# 7_DDR3L.net
KiCad netlist of a schematic drawn in Altium Designer
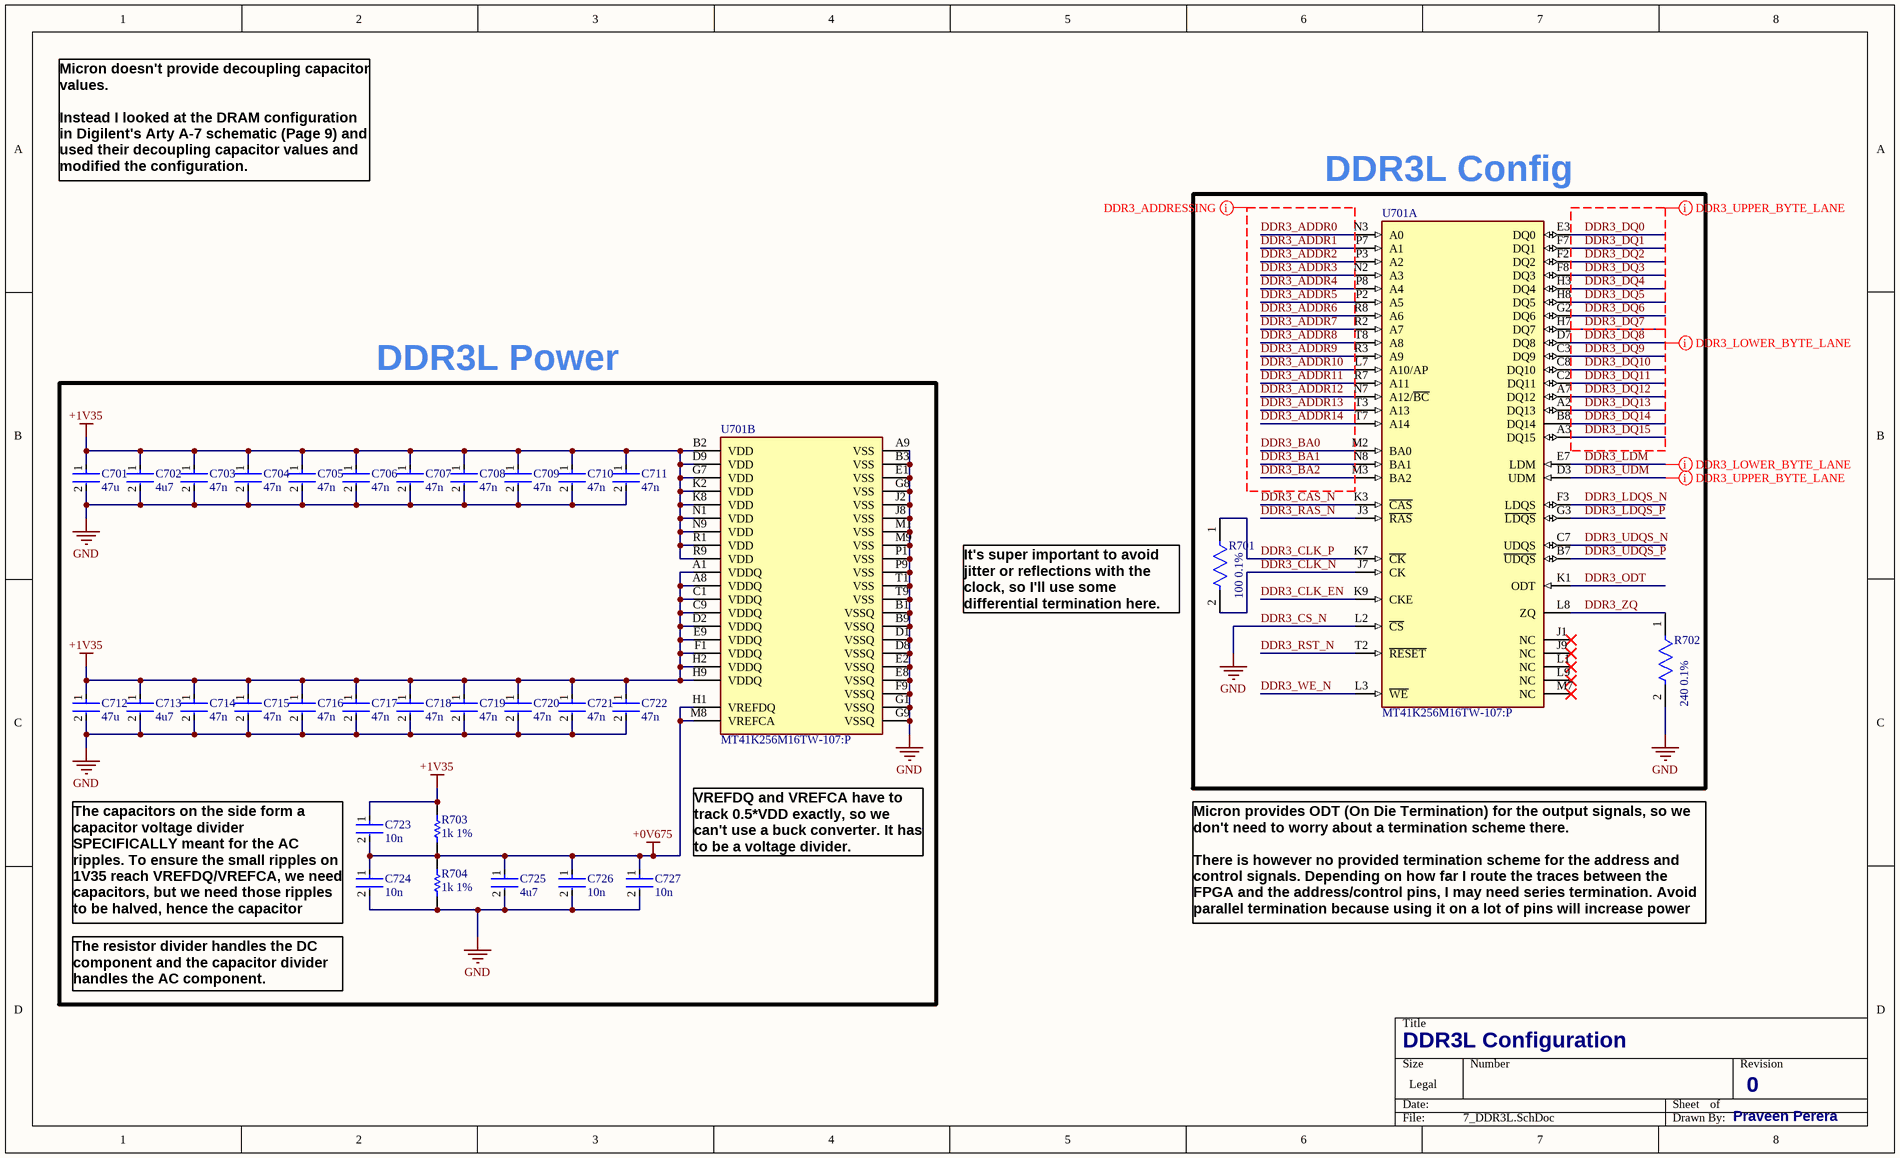
[diagram p0: 7_DDR3L.SchDoc]

(export (version "E")
  (design (tool "Eeschema 10.0.6"))
  (components
    (comp (ref "C701")
      (value "47u")
      (footprint "FP-GRM188-0_2-IPC_B")
      (fields (field (name "TOLERANCE") "20%"))
      (libsource (lib "Altium Content Vault") (part "11868f565c42a9108669ba33697ecf6"))
    )
    (comp (ref "C702")
      (value "4u7")
      (footprint "FP-CL829-IPC_C")
      (description "CL05A475MO5NUNC\r\n\r\nCap Ceramic 4.7uF 16V X5R ±20% SMD 0402 +85°C Paper T/R")
      (fields (field (name "TOLERANCE") "20%"))
      (libsource (lib "Altium Content Vault") (part "b4654b650e69147ec39a6b967a45e02"))
    )
    (comp (ref "C703")
      (value "47n")
      (footprint "FP-C0603-030-0_03-IPC_A")
      (description "C0603X5R1E473K030BB\r\n\r\nMultilayer Ceramic Capacitors 47nF ±10% 25V X5R SMD 0201")
      (fields (field (name "TOLERANCE") "10%"))
      (libsource (lib "Altium Content Vault") (part "02cd4be3c70576c341d710602a673aa"))
    )
    (comp (ref "C704")
      (value "47n")
      (footprint "FP-C0603-030-0_03-IPC_A")
      (description "C0603X5R1E473K030BB\r\n\r\nMultilayer Ceramic Capacitors 47nF ±10% 25V X5R SMD 0201")
      (fields (field (name "TOLERANCE") "10%"))
      (libsource (lib "Altium Content Vault") (part "02cd4be3c70576c341d710602a673aa"))
    )
    (comp (ref "C705")
      (value "47n")
      (footprint "FP-C0603-030-0_03-IPC_A")
      (description "C0603X5R1E473K030BB\r\n\r\nMultilayer Ceramic Capacitors 47nF ±10% 25V X5R SMD 0201")
      (fields (field (name "TOLERANCE") "10%"))
      (libsource (lib "Altium Content Vault") (part "02cd4be3c70576c341d710602a673aa"))
    )
    (comp (ref "C706")
      (value "47n")
      (footprint "FP-C0603-030-0_03-IPC_A")
      (description "C0603X5R1E473K030BB\r\n\r\nMultilayer Ceramic Capacitors 47nF ±10% 25V X5R SMD 0201")
      (fields (field (name "TOLERANCE") "10%"))
      (libsource (lib "Altium Content Vault") (part "02cd4be3c70576c341d710602a673aa"))
    )
    (comp (ref "C707")
      (value "47n")
      (footprint "FP-C0603-030-0_03-IPC_A")
      (description "C0603X5R1E473K030BB\r\n\r\nMultilayer Ceramic Capacitors 47nF ±10% 25V X5R SMD 0201")
      (fields (field (name "TOLERANCE") "10%"))
      (libsource (lib "Altium Content Vault") (part "02cd4be3c70576c341d710602a673aa"))
    )
    (comp (ref "C708")
      (value "47n")
      (footprint "FP-C0603-030-0_03-IPC_A")
      (description "C0603X5R1E473K030BB\r\n\r\nMultilayer Ceramic Capacitors 47nF ±10% 25V X5R SMD 0201")
      (fields (field (name "TOLERANCE") "10%"))
      (libsource (lib "Altium Content Vault") (part "02cd4be3c70576c341d710602a673aa"))
    )
    (comp (ref "C709")
      (value "47n")
      (footprint "FP-C0603-030-0_03-IPC_A")
      (description "C0603X5R1E473K030BB\r\n\r\nMultilayer Ceramic Capacitors 47nF ±10% 25V X5R SMD 0201")
      (fields (field (name "TOLERANCE") "10%"))
      (libsource (lib "Altium Content Vault") (part "02cd4be3c70576c341d710602a673aa"))
    )
    (comp (ref "C710")
      (value "47n")
      (footprint "FP-C0603-030-0_03-IPC_A")
      (description "C0603X5R1E473K030BB\r\n\r\nMultilayer Ceramic Capacitors 47nF ±10% 25V X5R SMD 0201")
      (fields (field (name "TOLERANCE") "10%"))
      (libsource (lib "Altium Content Vault") (part "02cd4be3c70576c341d710602a673aa"))
    )
    (comp (ref "C711")
      (value "47n")
      (footprint "FP-C0603-030-0_03-IPC_A")
      (description "C0603X5R1E473K030BB\r\n\r\nMultilayer Ceramic Capacitors 47nF ±10% 25V X5R SMD 0201")
      (fields (field (name "TOLERANCE") "10%"))
      (libsource (lib "Altium Content Vault") (part "02cd4be3c70576c341d710602a673aa"))
    )
    (comp (ref "C712")
      (value "47u")
      (footprint "FP-GRM188-0_2-IPC_B")
      (fields (field (name "TOLERANCE") "20%"))
      (libsource (lib "Altium Content Vault") (part "11868f565c42a9108669ba33697ecf6"))
    )
    (comp (ref "C713")
      (value "4u7")
      (footprint "FP-CL829-IPC_C")
      (description "CL05A475MO5NUNC\r\n\r\nCap Ceramic 4.7uF 16V X5R ±20% SMD 0402 +85°C Paper T/R")
      (fields (field (name "TOLERANCE") "20%"))
      (libsource (lib "Altium Content Vault") (part "b4654b650e69147ec39a6b967a45e02"))
    )
    (comp (ref "C714")
      (value "47n")
      (footprint "FP-C0603-030-0_03-IPC_A")
      (description "C0603X5R1E473K030BB\r\n\r\nMultilayer Ceramic Capacitors 47nF ±10% 25V X5R SMD 0201")
      (fields (field (name "TOLERANCE") "10%"))
      (libsource (lib "Altium Content Vault") (part "02cd4be3c70576c341d710602a673aa"))
    )
    (comp (ref "C715")
      (value "47n")
      (footprint "FP-C0603-030-0_03-IPC_A")
      (description "C0603X5R1E473K030BB\r\n\r\nMultilayer Ceramic Capacitors 47nF ±10% 25V X5R SMD 0201")
      (fields (field (name "TOLERANCE") "10%"))
      (libsource (lib "Altium Content Vault") (part "02cd4be3c70576c341d710602a673aa"))
    )
    (comp (ref "C716")
      (value "47n")
      (footprint "FP-C0603-030-0_03-IPC_A")
      (description "C0603X5R1E473K030BB\r\n\r\nMultilayer Ceramic Capacitors 47nF ±10% 25V X5R SMD 0201")
      (fields (field (name "TOLERANCE") "10%"))
      (libsource (lib "Altium Content Vault") (part "02cd4be3c70576c341d710602a673aa"))
    )
    (comp (ref "C717")
      (value "47n")
      (footprint "FP-C0603-030-0_03-IPC_A")
      (description "C0603X5R1E473K030BB\r\n\r\nMultilayer Ceramic Capacitors 47nF ±10% 25V X5R SMD 0201")
      (fields (field (name "TOLERANCE") "10%"))
      (libsource (lib "Altium Content Vault") (part "02cd4be3c70576c341d710602a673aa"))
    )
    (comp (ref "C718")
      (value "47n")
      (footprint "FP-C0603-030-0_03-IPC_A")
      (description "C0603X5R1E473K030BB\r\n\r\nMultilayer Ceramic Capacitors 47nF ±10% 25V X5R SMD 0201")
      (fields (field (name "TOLERANCE") "10%"))
      (libsource (lib "Altium Content Vault") (part "02cd4be3c70576c341d710602a673aa"))
    )
    (comp (ref "C719")
      (value "47n")
      (footprint "FP-C0603-030-0_03-IPC_A")
      (description "C0603X5R1E473K030BB\r\n\r\nMultilayer Ceramic Capacitors 47nF ±10% 25V X5R SMD 0201")
      (fields (field (name "TOLERANCE") "10%"))
      (libsource (lib "Altium Content Vault") (part "02cd4be3c70576c341d710602a673aa"))
    )
    (comp (ref "C720")
      (value "47n")
      (footprint "FP-C0603-030-0_03-IPC_A")
      (description "C0603X5R1E473K030BB\r\n\r\nMultilayer Ceramic Capacitors 47nF ±10% 25V X5R SMD 0201")
      (fields (field (name "TOLERANCE") "10%"))
      (libsource (lib "Altium Content Vault") (part "02cd4be3c70576c341d710602a673aa"))
    )
    (comp (ref "C721")
      (value "47n")
      (footprint "FP-C0603-030-0_03-IPC_A")
      (description "C0603X5R1E473K030BB\r\n\r\nMultilayer Ceramic Capacitors 47nF ±10% 25V X5R SMD 0201")
      (fields (field (name "TOLERANCE") "10%"))
      (libsource (lib "Altium Content Vault") (part "02cd4be3c70576c341d710602a673aa"))
    )
    (comp (ref "C722")
      (value "47n")
      (footprint "FP-C0603-030-0_03-IPC_A")
      (description "C0603X5R1E473K030BB\r\n\r\nMultilayer Ceramic Capacitors 47nF ±10% 25V X5R SMD 0201")
      (fields (field (name "TOLERANCE") "10%"))
      (libsource (lib "Altium Content Vault") (part "02cd4be3c70576c341d710602a673aa"))
    )
    (comp (ref "C723")
      (value "10n")
      (footprint "FP-GCM155-0_05-IPC_C")
      (description "GCM155R71E103KA37D\r\n\r\nCeramic Capacitor for Automotive 10nF ±10% 25VDC X7R 0402 Paper T/R")
      (fields (field (name "VOLTAGE") "25V") (field (name "TOLERANCE") "10%"))
      (libsource (lib "Altium Content Vault") (part "02cd4be3c70576c341d710602a673aa"))
    )
    (comp (ref "C724")
      (value "10n")
      (footprint "FP-GCM155-0_05-IPC_C")
      (description "GCM155R71E103KA37D\r\n\r\nCeramic Capacitor for Automotive 10nF ±10% 25VDC X7R 0402 Paper T/R")
      (fields (field (name "VOLTAGE") "25V") (field (name "TOLERANCE") "10%"))
      (libsource (lib "Altium Content Vault") (part "02cd4be3c70576c341d710602a673aa"))
    )
    (comp (ref "C725")
      (value "4u7")
      (footprint "FP-CL829-IPC_C")
      (description "CL05A475MO5NUNC\r\n\r\nCap Ceramic 4.7uF 16V X5R ±20% SMD 0402 +85°C Paper T/R")
      (fields (field (name "TOLERANCE") "20%"))
      (libsource (lib "Altium Content Vault") (part "b4654b650e69147ec39a6b967a45e02"))
    )
    (comp (ref "C726")
      (value "10n")
      (footprint "FP-GCM155-0_05-IPC_C")
      (description "GCM155R71E103KA37D\r\n\r\nCeramic Capacitor for Automotive 10nF ±10% 25VDC X7R 0402 Paper T/R")
      (fields (field (name "VOLTAGE") "25V") (field (name "TOLERANCE") "10%"))
      (libsource (lib "Altium Content Vault") (part "02cd4be3c70576c341d710602a673aa"))
    )
    (comp (ref "C727")
      (value "10n")
      (footprint "FP-GCM155-0_05-IPC_C")
      (description "GCM155R71E103KA37D\r\n\r\nCeramic Capacitor for Automotive 10nF ±10% 25VDC X7R 0402 Paper T/R")
      (fields (field (name "VOLTAGE") "25V") (field (name "TOLERANCE") "10%"))
      (libsource (lib "Altium Content Vault") (part "02cd4be3c70576c341d710602a673aa"))
    )
    (comp (ref "R701")
      (value "100 0.1%")
      (footprint "FP-ERA1A-IPC_B")
      (description "ERA-1AEB101C\r\n\r\nRES SMD 100 OHM 0.1% 1/20W 0201")
      (fields (field (name "TOLERANCE") "0.1%"))
      (libsource (lib "Altium Content Vault") (part "1029c3af85768c4190bb7ad29bc67b5"))
    )
    (comp (ref "R702")
      (value "240 0.1%")
      (footprint "FP-RT0201-MFG")
      (description "RT0201BRD07240RL\r\n\r\nRT0201 240Ω 0.05W 25 ppm/°C 0.10%")
      (fields
        (field (name "TOLERANCE") "0.001")
        (field (name "OCTOPART") "https://octopart.com/rt0201brd07240rl-yageo-87214234")
      )
      (libsource (lib "Altium Content Vault") (part "1029c3af85768c4190bb7ad29bc67b5"))
    )
    (comp (ref "R703")
      (value "1k 1%")
      (footprint "RESC0603X28X15NL05T05")
      (description "CRCW02011K00FKED")
      (fields (field (name "MANUFACTURER") "Vishay Dale"))
      (libsource (lib "Altium Content Vault") (part "RES"))
    )
    (comp (ref "R704")
      (value "1k 1%")
      (footprint "RESC0603X28X15NL05T05")
      (description "CRCW02011K00FKED")
      (fields (field (name "MANUFACTURER") "Vishay Dale"))
      (libsource (lib "Altium Content Vault") (part "RES"))
    )
    (comp (ref "U701")
      (value "MT41K256M16TW-107:P")
      (footprint "FP-TW-IPC_C")
      (description "IC DRAM 4G PARALLEL 96FBGA")
      (fields
        (field (name "MANUFACTURER") "Micron")
        (field (name "OCTOPART") "https://octopart.com/mt41k256m16tw-107%3Ap-micron-66533852")
      )
      (libsource (lib "Altium Content Vault") (part "cdaccbdf9e98e5f2804aaab7a1ea706"))
    )
  )
  (nets
    (net (code "1") (name "+0V675") (class "Default")
      (node (ref "C723") (pin "2") (pinfunction "2_2") (pintype "passive"))
      (node (ref "C724") (pin "1") (pinfunction "1_1") (pintype "passive"))
      (node (ref "C725") (pin "1") (pinfunction "1_1") (pintype "passive"))
      (node (ref "C726") (pin "1") (pinfunction "1_1") (pintype "passive"))
      (node (ref "C727") (pin "1") (pinfunction "1_1") (pintype "passive"))
      (node (ref "R703") (pin "1") (pinfunction "1_1") (pintype "passive"))
      (node (ref "R704") (pin "2") (pinfunction "2_2") (pintype "passive"))
      (node (ref "U701") (pin "H1") (pinfunction "VREFDQ_H1") (pintype "power_in"))
      (node (ref "U701") (pin "M8") (pinfunction "VREFCA_M8") (pintype "power_in"))
    )
    (net (code "2") (name "+1V35") (class "Default")
      (node (ref "C701") (pin "1") (pinfunction "1_1") (pintype "passive"))
      (node (ref "C702") (pin "1") (pinfunction "1_1") (pintype "passive"))
      (node (ref "C703") (pin "1") (pinfunction "1_1") (pintype "passive"))
      (node (ref "C704") (pin "1") (pinfunction "1_1") (pintype "passive"))
      (node (ref "C705") (pin "1") (pinfunction "1_1") (pintype "passive"))
      (node (ref "C706") (pin "1") (pinfunction "1_1") (pintype "passive"))
      (node (ref "C707") (pin "1") (pinfunction "1_1") (pintype "passive"))
      (node (ref "C708") (pin "1") (pinfunction "1_1") (pintype "passive"))
      (node (ref "C709") (pin "1") (pinfunction "1_1") (pintype "passive"))
      (node (ref "C710") (pin "1") (pinfunction "1_1") (pintype "passive"))
      (node (ref "C711") (pin "1") (pinfunction "1_1") (pintype "passive"))
      (node (ref "C712") (pin "1") (pinfunction "1_1") (pintype "passive"))
      (node (ref "C713") (pin "1") (pinfunction "1_1") (pintype "passive"))
      (node (ref "C714") (pin "1") (pinfunction "1_1") (pintype "passive"))
      (node (ref "C715") (pin "1") (pinfunction "1_1") (pintype "passive"))
      (node (ref "C716") (pin "1") (pinfunction "1_1") (pintype "passive"))
      (node (ref "C717") (pin "1") (pinfunction "1_1") (pintype "passive"))
      (node (ref "C718") (pin "1") (pinfunction "1_1") (pintype "passive"))
      (node (ref "C719") (pin "1") (pinfunction "1_1") (pintype "passive"))
      (node (ref "C720") (pin "1") (pinfunction "1_1") (pintype "passive"))
      (node (ref "C721") (pin "1") (pinfunction "1_1") (pintype "passive"))
      (node (ref "C722") (pin "1") (pinfunction "1_1") (pintype "passive"))
      (node (ref "C723") (pin "1") (pinfunction "1_1") (pintype "passive"))
      (node (ref "R703") (pin "2") (pinfunction "2_2") (pintype "passive"))
      (node (ref "U701") (pin "A1") (pinfunction "VDDQ_A1") (pintype "power_in"))
      (node (ref "U701") (pin "A8") (pinfunction "VDDQ_A8") (pintype "power_in"))
      (node (ref "U701") (pin "B2") (pinfunction "VDD_B2") (pintype "power_in"))
      (node (ref "U701") (pin "C1") (pinfunction "VDDQ_C1") (pintype "power_in"))
      (node (ref "U701") (pin "C9") (pinfunction "VDDQ_C9") (pintype "power_in"))
      (node (ref "U701") (pin "D2") (pinfunction "VDDQ_D2") (pintype "power_in"))
      (node (ref "U701") (pin "D9") (pinfunction "VDD_D9") (pintype "power_in"))
      (node (ref "U701") (pin "E9") (pinfunction "VDDQ_E9") (pintype "power_in"))
      (node (ref "U701") (pin "F1") (pinfunction "VDDQ_F1") (pintype "power_in"))
      (node (ref "U701") (pin "G7") (pinfunction "VDD_G7") (pintype "power_in"))
      (node (ref "U701") (pin "H2") (pinfunction "VDDQ_H2") (pintype "power_in"))
      (node (ref "U701") (pin "H9") (pinfunction "VDDQ_H9") (pintype "power_in"))
      (node (ref "U701") (pin "K2") (pinfunction "VDD_K2") (pintype "power_in"))
      (node (ref "U701") (pin "K8") (pinfunction "VDD_K8") (pintype "power_in"))
      (node (ref "U701") (pin "N1") (pinfunction "VDD_N1") (pintype "power_in"))
      (node (ref "U701") (pin "N9") (pinfunction "VDD_N9") (pintype "power_in"))
      (node (ref "U701") (pin "R1") (pinfunction "VDD_R1") (pintype "power_in"))
      (node (ref "U701") (pin "R9") (pinfunction "VDD_R9") (pintype "power_in"))
    )
    (net (code "3") (name "/DDR3_ADDR0") (class "Default")
      (node (ref "U701") (pin "N3") (pinfunction "A0_N3") (pintype "input"))
    )
    (net (code "4") (name "/DDR3_ADDR1") (class "Default")
      (node (ref "U701") (pin "P7") (pinfunction "A1_P7") (pintype "input"))
    )
    (net (code "5") (name "/DDR3_ADDR2") (class "Default")
      (node (ref "U701") (pin "P3") (pinfunction "A2_P3") (pintype "input"))
    )
    (net (code "6") (name "/DDR3_ADDR3") (class "Default")
      (node (ref "U701") (pin "N2") (pinfunction "A3_N2") (pintype "input"))
    )
    (net (code "7") (name "/DDR3_ADDR4") (class "Default")
      (node (ref "U701") (pin "P8") (pinfunction "A4_P8") (pintype "input"))
    )
    (net (code "8") (name "/DDR3_ADDR5") (class "Default")
      (node (ref "U701") (pin "P2") (pinfunction "A5_P2") (pintype "input"))
    )
    (net (code "9") (name "/DDR3_ADDR6") (class "Default")
      (node (ref "U701") (pin "R8") (pinfunction "A6_R8") (pintype "input"))
    )
    (net (code "10") (name "/DDR3_ADDR7") (class "Default")
      (node (ref "U701") (pin "R2") (pinfunction "A7_R2") (pintype "input"))
    )
    (net (code "11") (name "/DDR3_ADDR8") (class "Default")
      (node (ref "U701") (pin "T8") (pinfunction "A8_T8") (pintype "input"))
    )
    (net (code "12") (name "/DDR3_ADDR9") (class "Default")
      (node (ref "U701") (pin "R3") (pinfunction "A9_R3") (pintype "input"))
    )
    (net (code "13") (name "/DDR3_ADDR10") (class "Default")
      (node (ref "U701") (pin "L7") (pinfunction "A10/AP_L7") (pintype "input"))
    )
    (net (code "14") (name "/DDR3_ADDR11") (class "Default")
      (node (ref "U701") (pin "R7") (pinfunction "A11_R7") (pintype "input"))
    )
    (net (code "15") (name "/DDR3_ADDR12") (class "Default")
      (node (ref "U701") (pin "N7") (pinfunction "A12/~{BC}_N7") (pintype "input"))
    )
    (net (code "16") (name "/DDR3_ADDR13") (class "Default")
      (node (ref "U701") (pin "T3") (pinfunction "A13_T3") (pintype "input"))
    )
    (net (code "17") (name "/DDR3_ADDR14") (class "Default")
      (node (ref "U701") (pin "T7") (pinfunction "A14_T7") (pintype "input"))
    )
    (net (code "18") (name "/DDR3_BA0") (class "Default")
      (node (ref "U701") (pin "M2") (pinfunction "BA0_M2") (pintype "input"))
    )
    (net (code "19") (name "/DDR3_BA1") (class "Default")
      (node (ref "U701") (pin "N8") (pinfunction "BA1_N8") (pintype "input"))
    )
    (net (code "20") (name "/DDR3_BA2") (class "Default")
      (node (ref "U701") (pin "M3") (pinfunction "BA2_M3") (pintype "input"))
    )
    (net (code "21") (name "/DDR3_CAS_N") (class "Default")
      (node (ref "U701") (pin "K3") (pinfunction "~{CAS}_K3") (pintype "input"))
    )
    (net (code "22") (name "/DDR3_CLK_EN") (class "Default")
      (node (ref "U701") (pin "K9") (pinfunction "CKE_K9") (pintype "input"))
    )
    (net (code "23") (name "/DDR3_CLK_N") (class "Default")
      (node (ref "R701") (pin "2") (pinfunction "2_2") (pintype "passive"))
      (node (ref "U701") (pin "J7") (pinfunction "CK_J7") (pintype "input"))
    )
    (net (code "24") (name "/DDR3_CLK_P") (class "Default")
      (node (ref "R701") (pin "1") (pinfunction "1_1") (pintype "passive"))
      (node (ref "U701") (pin "K7") (pinfunction "~{CK}_K7") (pintype "input"))
    )
    (net (code "25") (name "/DDR3_DQ0") (class "Default")
      (node (ref "U701") (pin "E3") (pinfunction "DQ0_E3") (pintype "bidirectional"))
    )
    (net (code "26") (name "/DDR3_DQ1") (class "Default")
      (node (ref "U701") (pin "F7") (pinfunction "DQ1_F7") (pintype "bidirectional"))
    )
    (net (code "27") (name "/DDR3_DQ2") (class "Default")
      (node (ref "U701") (pin "F2") (pinfunction "DQ2_F2") (pintype "bidirectional"))
    )
    (net (code "28") (name "/DDR3_DQ3") (class "Default")
      (node (ref "U701") (pin "F8") (pinfunction "DQ3_F8") (pintype "bidirectional"))
    )
    (net (code "29") (name "/DDR3_DQ4") (class "Default")
      (node (ref "U701") (pin "H3") (pinfunction "DQ4_H3") (pintype "bidirectional"))
    )
    (net (code "30") (name "/DDR3_DQ5") (class "Default")
      (node (ref "U701") (pin "H8") (pinfunction "DQ5_H8") (pintype "bidirectional"))
    )
    (net (code "31") (name "/DDR3_DQ6") (class "Default")
      (node (ref "U701") (pin "G2") (pinfunction "DQ6_G2") (pintype "bidirectional"))
    )
    (net (code "32") (name "/DDR3_DQ7") (class "Default")
      (node (ref "U701") (pin "H7") (pinfunction "DQ7_H7") (pintype "bidirectional"))
    )
    (net (code "33") (name "/DDR3_DQ8") (class "Default")
      (node (ref "U701") (pin "D7") (pinfunction "DQ8_D7") (pintype "bidirectional"))
    )
    (net (code "34") (name "/DDR3_DQ9") (class "Default")
      (node (ref "U701") (pin "C3") (pinfunction "DQ9_C3") (pintype "bidirectional"))
    )
    (net (code "35") (name "/DDR3_DQ10") (class "Default")
      (node (ref "U701") (pin "C8") (pinfunction "DQ10_C8") (pintype "bidirectional"))
    )
    (net (code "36") (name "/DDR3_DQ11") (class "Default")
      (node (ref "U701") (pin "C2") (pinfunction "DQ11_C2") (pintype "bidirectional"))
    )
    (net (code "37") (name "/DDR3_DQ12") (class "Default")
      (node (ref "U701") (pin "A7") (pinfunction "DQ12_A7") (pintype "bidirectional"))
    )
    (net (code "38") (name "/DDR3_DQ13") (class "Default")
      (node (ref "U701") (pin "A2") (pinfunction "DQ13_A2") (pintype "bidirectional"))
    )
    (net (code "39") (name "/DDR3_DQ14") (class "Default")
      (node (ref "U701") (pin "B8") (pinfunction "DQ14_B8") (pintype "power_in"))
    )
    (net (code "40") (name "/DDR3_DQ15") (class "Default")
      (node (ref "U701") (pin "A3") (pinfunction "DQ15_A3") (pintype "bidirectional"))
    )
    (net (code "41") (name "/DDR3_LDM") (class "Default")
      (node (ref "U701") (pin "E7") (pinfunction "LDM_E7") (pintype "input"))
    )
    (net (code "42") (name "/DDR3_LDQS_N") (class "Default")
      (node (ref "U701") (pin "F3") (pinfunction "LDQS_F3") (pintype "bidirectional"))
    )
    (net (code "43") (name "/DDR3_LDQS_P") (class "Default")
      (node (ref "U701") (pin "G3") (pinfunction "~{LDQS}_G3") (pintype "bidirectional"))
    )
    (net (code "44") (name "/DDR3_ODT") (class "Default")
      (node (ref "U701") (pin "K1") (pinfunction "ODT_K1") (pintype "input"))
    )
    (net (code "45") (name "/DDR3_RAS_N") (class "Default")
      (node (ref "U701") (pin "J3") (pinfunction "~{RAS}_J3") (pintype "input"))
    )
    (net (code "46") (name "/DDR3_RST_N") (class "Default")
      (node (ref "U701") (pin "T2") (pinfunction "~{RESET}_T2") (pintype "input"))
    )
    (net (code "47") (name "/DDR3_UDM") (class "Default")
      (node (ref "U701") (pin "D3") (pinfunction "UDM_D3") (pintype "input"))
    )
    (net (code "48") (name "/DDR3_UDQS_N") (class "Default")
      (node (ref "U701") (pin "C7") (pinfunction "UDQS_C7") (pintype "bidirectional"))
    )
    (net (code "49") (name "/DDR3_UDQS_P") (class "Default")
      (node (ref "U701") (pin "B7") (pinfunction "~{UDQS}_B7") (pintype "bidirectional"))
    )
    (net (code "50") (name "/DDR3_WE_N") (class "Default")
      (node (ref "U701") (pin "L3") (pinfunction "~{WE}_L3") (pintype "input"))
    )
    (net (code "51") (name "/DDR3_ZQ") (class "Default")
      (node (ref "R702") (pin "1") (pinfunction "1_1") (pintype "passive"))
      (node (ref "U701") (pin "L8") (pinfunction "ZQ_L8") (pintype "passive"))
    )
    (net (code "52") (name "GND") (class "Default")
      (node (ref "C701") (pin "2") (pinfunction "2_2") (pintype "passive"))
      (node (ref "C702") (pin "2") (pinfunction "2_2") (pintype "passive"))
      (node (ref "C703") (pin "2") (pinfunction "2_2") (pintype "passive"))
      (node (ref "C704") (pin "2") (pinfunction "2_2") (pintype "passive"))
      (node (ref "C705") (pin "2") (pinfunction "2_2") (pintype "passive"))
      (node (ref "C706") (pin "2") (pinfunction "2_2") (pintype "passive"))
      (node (ref "C707") (pin "2") (pinfunction "2_2") (pintype "passive"))
      (node (ref "C708") (pin "2") (pinfunction "2_2") (pintype "passive"))
      (node (ref "C709") (pin "2") (pinfunction "2_2") (pintype "passive"))
      (node (ref "C710") (pin "2") (pinfunction "2_2") (pintype "passive"))
      (node (ref "C711") (pin "2") (pinfunction "2_2") (pintype "passive"))
      (node (ref "C712") (pin "2") (pinfunction "2_2") (pintype "passive"))
      (node (ref "C713") (pin "2") (pinfunction "2_2") (pintype "passive"))
      (node (ref "C714") (pin "2") (pinfunction "2_2") (pintype "passive"))
      (node (ref "C715") (pin "2") (pinfunction "2_2") (pintype "passive"))
      (node (ref "C716") (pin "2") (pinfunction "2_2") (pintype "passive"))
      (node (ref "C717") (pin "2") (pinfunction "2_2") (pintype "passive"))
      (node (ref "C718") (pin "2") (pinfunction "2_2") (pintype "passive"))
      (node (ref "C719") (pin "2") (pinfunction "2_2") (pintype "passive"))
      (node (ref "C720") (pin "2") (pinfunction "2_2") (pintype "passive"))
      (node (ref "C721") (pin "2") (pinfunction "2_2") (pintype "passive"))
      (node (ref "C722") (pin "2") (pinfunction "2_2") (pintype "passive"))
      (node (ref "C724") (pin "2") (pinfunction "2_2") (pintype "passive"))
      (node (ref "C725") (pin "2") (pinfunction "2_2") (pintype "passive"))
      (node (ref "C726") (pin "2") (pinfunction "2_2") (pintype "passive"))
      (node (ref "C727") (pin "2") (pinfunction "2_2") (pintype "passive"))
      (node (ref "R702") (pin "2") (pinfunction "2_2") (pintype "passive"))
      (node (ref "R704") (pin "1") (pinfunction "1_1") (pintype "passive"))
      (node (ref "U701") (pin "A9") (pinfunction "VSS_A9") (pintype "power_in"))
      (node (ref "U701") (pin "B1") (pinfunction "VSSQ_B1") (pintype "power_in"))
      (node (ref "U701") (pin "B3") (pinfunction "VSS_B3") (pintype "power_in"))
      (node (ref "U701") (pin "B9") (pinfunction "VSSQ_B9") (pintype "power_in"))
      (node (ref "U701") (pin "D1") (pinfunction "VSSQ_D1") (pintype "power_in"))
      (node (ref "U701") (pin "D8") (pinfunction "VSSQ_D8") (pintype "power_in"))
      (node (ref "U701") (pin "E1") (pinfunction "VSS_E1") (pintype "power_in"))
      (node (ref "U701") (pin "E2") (pinfunction "VSSQ_E2") (pintype "power_in"))
      (node (ref "U701") (pin "E8") (pinfunction "VSSQ_E8") (pintype "power_in"))
      (node (ref "U701") (pin "F9") (pinfunction "VSSQ_F9") (pintype "power_in"))
      (node (ref "U701") (pin "G1") (pinfunction "VSSQ_G1") (pintype "power_in"))
      (node (ref "U701") (pin "G8") (pinfunction "VSS_G8") (pintype "power_in"))
      (node (ref "U701") (pin "G9") (pinfunction "VSSQ_G9") (pintype "power_in"))
      (node (ref "U701") (pin "J2") (pinfunction "VSS_J2") (pintype "power_in"))
      (node (ref "U701") (pin "J8") (pinfunction "VSS_J8") (pintype "power_in"))
      (node (ref "U701") (pin "L2") (pinfunction "~{CS}_L2") (pintype "input"))
      (node (ref "U701") (pin "M1") (pinfunction "VSS_M1") (pintype "power_in"))
      (node (ref "U701") (pin "M9") (pinfunction "VSS_M9") (pintype "power_in"))
      (node (ref "U701") (pin "P1") (pinfunction "VSS_P1") (pintype "power_in"))
      (node (ref "U701") (pin "P9") (pinfunction "VSS_P9") (pintype "power_in"))
      (node (ref "U701") (pin "T1") (pinfunction "VSS_T1") (pintype "power_in"))
      (node (ref "U701") (pin "T9") (pinfunction "VSS_T9") (pintype "power_in"))
    )
    (net (code "53") (name "unconnected-(U701A-NC-PadJ1)") (class "Default")
      (node (ref "U701") (pin "J1") (pinfunction "NC_J1") (pintype "passive+no_connect"))
    )
    (net (code "54") (name "unconnected-(U701A-NC-PadJ9)") (class "Default")
      (node (ref "U701") (pin "J9") (pinfunction "NC_J9") (pintype "passive+no_connect"))
    )
    (net (code "55") (name "unconnected-(U701A-NC-PadL1)") (class "Default")
      (node (ref "U701") (pin "L1") (pinfunction "NC_L1") (pintype "passive+no_connect"))
    )
    (net (code "56") (name "unconnected-(U701A-NC-PadL9)") (class "Default")
      (node (ref "U701") (pin "L9") (pinfunction "NC_L9") (pintype "passive+no_connect"))
    )
    (net (code "57") (name "unconnected-(U701A-NC-PadM7)") (class "Default")
      (node (ref "U701") (pin "M7") (pinfunction "NC_M7") (pintype "passive+no_connect"))
    )
  )
)
